# LLU_PCB_V2.net
KiCad netlist of a schematic drawn in EasyEDA
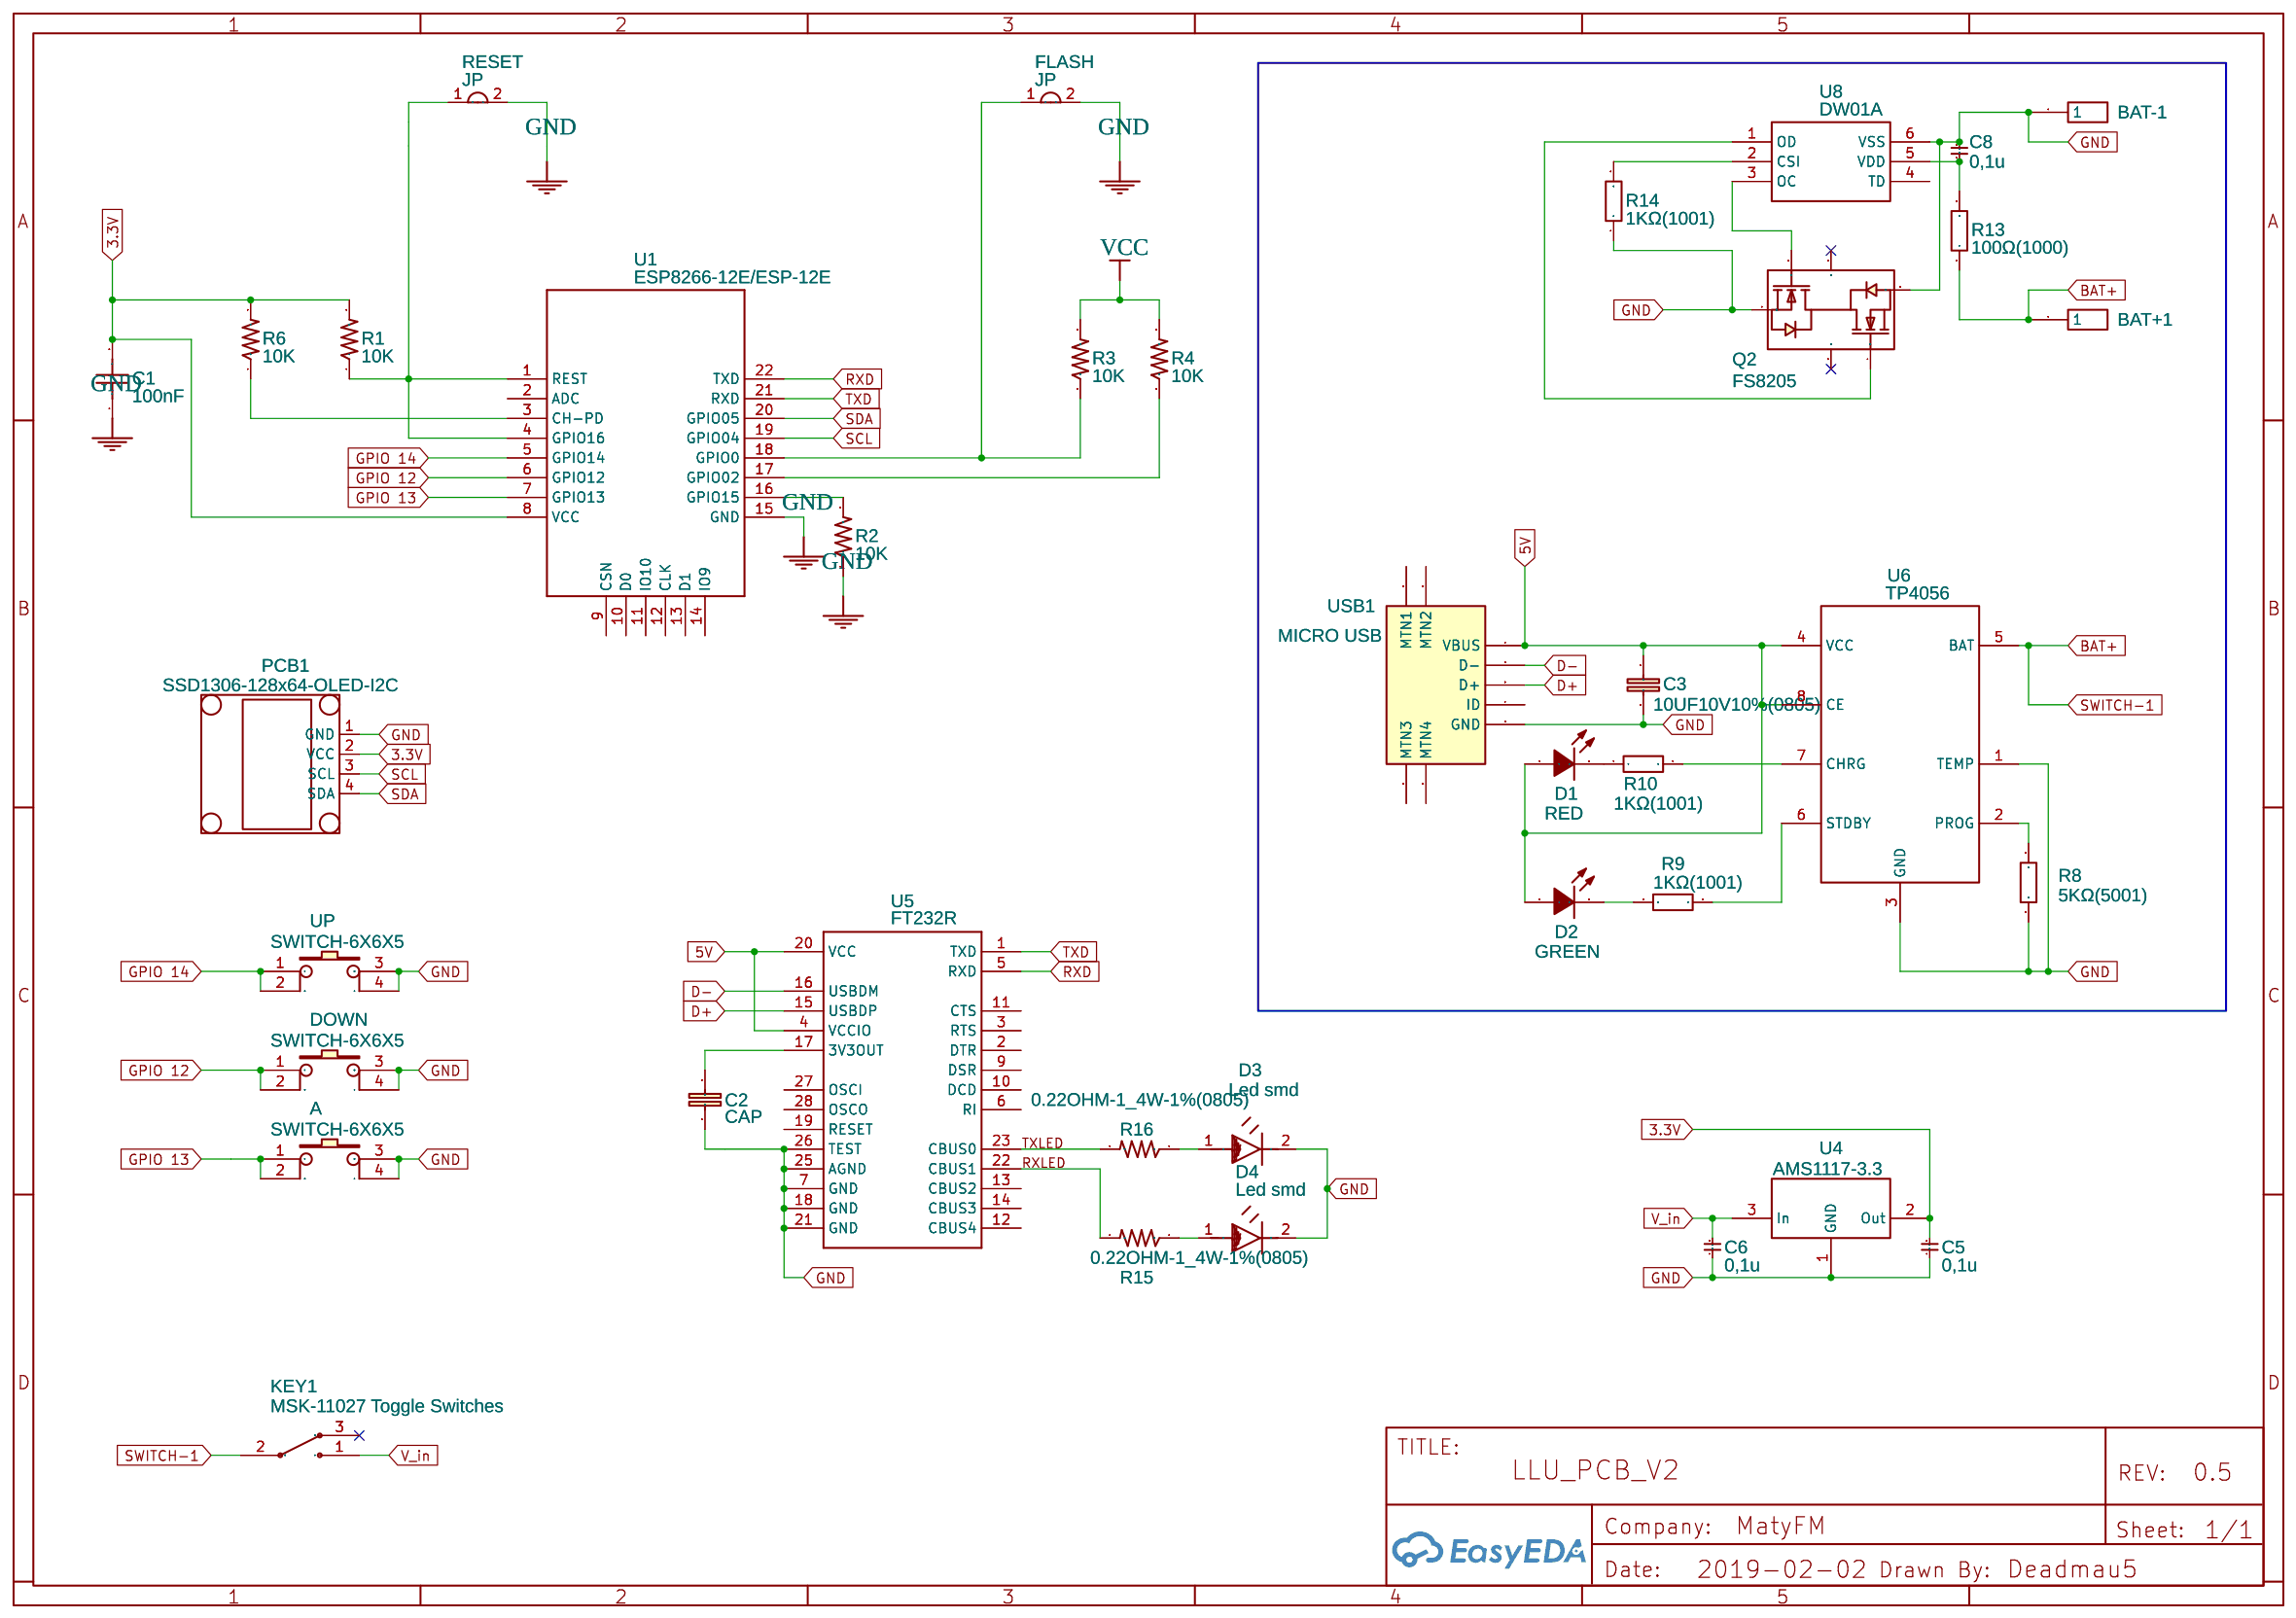
[diagram p0: schematic sheet]

(export (version "E")
  (design (tool "Eeschema 10.0.6"))
  (components
    (comp (ref "A")
      (value "SWITCH-6X6X5")
      (fields
        (field (name "BOM_Manufacturer Part") "SWITCH-6X6X5_TH")
        (field (name "BOM_Supplier Part") "C69330")
      )
      (libsource (lib "") (part "Unknown_155_590"))
    )
    (comp (ref "BAT+1")
      (value "BAT+")
      (fields
        (field (name "BOM_Manufacturer Part") "Header 1*1P")
        (field (name "BOM_Supplier Part") "C81276")
      )
      (libsource (lib "") (part "Unknown_1040_155"))
    )
    (comp (ref "BAT-1")
      (value "BAT-")
      (fields
        (field (name "BOM_Manufacturer Part") "Header 1*1P")
        (field (name "BOM_Supplier Part") "C81276")
      )
      (libsource (lib "") (part "Unknown_1040_50"))
    )
    (comp (ref "C1")
      (value "100nF")
      (fields
        (field (name "BOM_Manufacturer Part") "GRM2165C1H122JA01D")
        (field (name "BOM_Supplier Part") "C97898")
      )
      (libsource (lib "") (part "Capasitor_0805"))
    )
    (comp (ref "C2")
      (value "CAP")
      (fields (field (name "BOM_Manufacturer Part") "?"))
      (libsource (lib "") (part "Unknown_350_555"))
    )
    (comp (ref "C3")
      (value "10UF10V10%(0805)")
      (fields (field (name "BOM_Manufacturer Part") "?"))
      (libsource (lib "") (part "Unknown_825_345"))
    )
    (comp (ref "C5")
      (value "0,1u")
      (fields
        (field (name "BOM_Manufacturer Part") "0805F106M250NT")
        (field (name "BOM_Supplier Part") "C48181")
      )
      (libsource (lib "") (part "Unknown_970_620"))
    )
    (comp (ref "C6")
      (value "0,1u")
      (fields
        (field (name "BOM_Manufacturer Part") "0805F106M250NT")
        (field (name "BOM_Supplier Part") "C48181")
      )
      (libsource (lib "") (part "Unknown_860_620"))
    )
    (comp (ref "C8")
      (value "0,1u")
      (fields
        (field (name "BOM_Manufacturer Part") "0805F106M250NT")
        (field (name "BOM_Supplier Part") "C48181")
      )
      (libsource (lib "") (part "Unknown_985_65"))
    )
    (comp (ref "D1")
      (value "RED")
      (fields
        (field (name "BOM_Manufacturer Part") "LTST-C191KRKT")
        (field (name "BOM_Supplier Part") "C125099")
      )
      (libsource (lib "") (part "Unknown_785_375"))
    )
    (comp (ref "D2")
      (value "GREEN")
      (fields
        (field (name "BOM_Manufacturer Part") "LTST-C193TGKT-5A")
        (field (name "BOM_Supplier Part") "C12065")
      )
      (libsource (lib "") (part "Unknown_785_445"))
    )
    (comp (ref "D3") (value "Led smd") (libsource (lib "") (part "Unknown_600_575")))
    (comp (ref "D4") (value "Led smd") (libsource (lib "") (part "Unknown_600_620")))
    (comp (ref "DOWN")
      (value "SWITCH-6X6X5")
      (fields
        (field (name "BOM_Manufacturer Part") "SWITCH-6X6X5_TH")
        (field (name "BOM_Supplier Part") "C69330")
      )
      (libsource (lib "") (part "Unknown_155_545"))
    )
    (comp (ref "FLASH")
      (value "JP")
      (fields (field (name "BOM_Manufacturer Part") "SMD-Jumper"))
      (libsource (lib "") (part "Unknown_525_45"))
    )
    (comp (ref "KEY1") (value "MSK-11027 Toggle Switches") (libsource (lib "") (part "Unknown_155_720")))
    (comp (ref "PCB1")
      (value "SSD1306-128x64-OLED-I2C")
      (fields (field (name "BOM_Manufacturer Part") "?"))
      (libsource (lib "") (part "Unknown_135_375"))
    )
    (comp (ref "Q2")
      (value "FS8205")
      (fields (field (name "BOM_Supplier Part") "C32254"))
      (libsource (lib "") (part "Unknown_920_150"))
    )
    (comp (ref "R1")
      (value "10K")
      (fields (field (name "BOM_Manufacturer Part") "?"))
      (libsource (lib "") (part "Unknown_170_165"))
    )
    (comp (ref "R2")
      (value "10K")
      (fields (field (name "BOM_Manufacturer Part") "?"))
      (libsource (lib "") (part "Unknown_420_265"))
    )
    (comp (ref "R3")
      (value "10K")
      (fields (field (name "BOM_Manufacturer Part") "?"))
      (libsource (lib "") (part "Unknown_540_175"))
    )
    (comp (ref "R4")
      (value "10K")
      (fields (field (name "BOM_Manufacturer Part") "?"))
      (libsource (lib "") (part "Unknown_580_175"))
    )
    (comp (ref "R6")
      (value "10K")
      (fields (field (name "BOM_Manufacturer Part") "?"))
      (libsource (lib "") (part "Unknown_120_165"))
    )
    (comp (ref "R8")
      (value "5KΩ(5001)")
      (fields
        (field (name "BOM_Manufacturer Part") "RT0805BRD075K1L")
        (field (name "BOM_Supplier Part") "C122968")
      )
      (libsource (lib "") (part "RT0805BRD075K1L"))
    )
    (comp (ref "R9")
      (value "1KΩ(1001)")
      (fields
        (field (name "BOM_Manufacturer Part") "RT0805BRD071KL")
        (field (name "BOM_Supplier Part") "C110774")
      )
      (libsource (lib "") (part "RT0805BRD071KL"))
    )
    (comp (ref "R10")
      (value "1KΩ(1001)")
      (fields
        (field (name "BOM_Manufacturer Part") "RT0805BRD071KL")
        (field (name "BOM_Supplier Part") "C110774")
      )
      (libsource (lib "") (part "RT0805BRD071KL"))
    )
    (comp (ref "R13")
      (value "100Ω(1000)")
      (fields
        (field (name "BOM_Manufacturer Part") "CR0805F81000G")
        (field (name "BOM_Supplier Part") "C101403")
      )
      (libsource (lib "") (part "CR0805F81000G"))
    )
    (comp (ref "R14")
      (value "1KΩ(1001)")
      (fields
        (field (name "BOM_Manufacturer Part") "RTT051001FTP")
        (field (name "BOM_Supplier Part") "C103903")
      )
      (libsource (lib "") (part "RTT051001FTP"))
    )
    (comp (ref "R15")
      (value "0.22OHM-1_4W-1%(0805)")
      (fields (field (name "BOM_Manufacturer Part") "?"))
      (libsource (lib "") (part "Unknown_570_620"))
    )
    (comp (ref "R16")
      (value "0.22OHM-1_4W-1%(0805)")
      (fields (field (name "BOM_Manufacturer Part") "?"))
      (libsource (lib "") (part "Unknown_570_575"))
    )
    (comp (ref "RESET")
      (value "JP")
      (fields (field (name "BOM_Manufacturer Part") "SMD-Jumper"))
      (libsource (lib "") (part "Unknown_235_45"))
    )
    (comp (ref "U1")
      (value "ESP8266-12E/ESP-12E")
      (fields (field (name "BOM_Supplier Part") "317060015"))
      (libsource (lib "") (part "Unknown_320_235"))
    )
    (comp (ref "U4")
      (value "AMS1117-3.3")
      (fields (field (name "BOM_Manufacturer Part") "AMS1117-5.0") (field (name "BOM_Supplier Part") "C6187"))
      (libsource (lib "") (part "Unknown_920_610"))
    )
    (comp (ref "U5")
      (value "FT232R")
      (fields (field (name "BOM_Manufacturer Part") "?"))
      (libsource (lib "") (part "Unknown_450_545"))
    )
    (comp (ref "U6")
      (value "TP4056")
      (fields (field (name "BOM_Supplier Part") "C16581"))
      (libsource (lib "") (part "Unknown_955_380"))
    )
    (comp (ref "U8")
      (value "DW01A")
      (fields (field (name "BOM_Supplier Part") "C85680"))
      (libsource (lib "") (part "Unknown_920_75"))
    )
    (comp (ref "UP")
      (value "SWITCH-6X6X5")
      (fields
        (field (name "BOM_Manufacturer Part") "SWITCH-6X6X5_TH")
        (field (name "BOM_Supplier Part") "C69330")
      )
      (libsource (lib "") (part "Unknown_155_495"))
    )
    (comp (ref "USB1")
      (value "MICRO USB")
      (fields
        (field (name "BOM_Manufacturer Part") "MICRO USB 5S B")
        (field (name "BOM_Supplier Part") "C10418")
      )
      (libsource (lib "") (part "Unknown_715_340"))
    )
  )
  (nets
    (net (code "1") (name "3.3V") (class "Default")
      (node (ref "C1") (pin "2") (pinfunction "2_2") (pintype "unspecified"))
      (node (ref "C5") (pin "2") (pinfunction "2_2") (pintype "input"))
      (node (ref "PCB1") (pin "2") (pinfunction "VCC_2") (pintype "input"))
      (node (ref "R1") (pin "2") (pinfunction "2_2") (pintype "unspecified"))
      (node (ref "R6") (pin "2") (pinfunction "2_2") (pintype "unspecified"))
      (node (ref "U1") (pin "8") (pinfunction "VCC_8") (pintype "unspecified"))
      (node (ref "U4") (pin "2") (pinfunction "Out_2") (pintype "unspecified"))
    )
    (net (code "2") (name "5V") (class "Default")
      (node (ref "C3") (pin "1") (pinfunction "1_1") (pintype "unspecified"))
      (node (ref "D1") (pin "1") (pinfunction "A_1") (pintype "unspecified"))
      (node (ref "D2") (pin "1") (pinfunction "A_1") (pintype "unspecified"))
      (node (ref "U5") (pin "20") (pinfunction "VCC_20") (pintype "passive"))
      (node (ref "U5") (pin "4") (pinfunction "VCCIO_4") (pintype "passive"))
      (node (ref "U6") (pin "4") (pinfunction "VCC_4") (pintype "unspecified"))
      (node (ref "U6") (pin "8") (pinfunction "CE_8") (pintype "unspecified"))
      (node (ref "USB1") (pin "1") (pinfunction "VBUS_1") (pintype "input"))
    )
    (net (code "3") (name "BAT+") (class "Default")
      (node (ref "BAT+1") (pin "1") (pinfunction "1_1") (pintype "input"))
      (node (ref "KEY1") (pin "2") (pinfunction "2_2") (pintype "unspecified"))
      (node (ref "R13") (pin "1") (pinfunction "1_1") (pintype "input"))
      (node (ref "U6") (pin "5") (pinfunction "BAT_5") (pintype "unspecified"))
    )
    (net (code "4") (name "D+") (class "Default")
      (node (ref "U5") (pin "15") (pinfunction "USBDP_15") (pintype "unspecified"))
      (node (ref "USB1") (pin "3") (pinfunction "D+_3") (pintype "input"))
    )
    (net (code "5") (name "D-") (class "Default")
      (node (ref "U5") (pin "16") (pinfunction "USBDM_16") (pintype "unspecified"))
      (node (ref "USB1") (pin "2") (pinfunction "D-_2") (pintype "input"))
    )
    (net (code "6") (name "GND") (class "Default")
      (node (ref "A") (pin "3") (pinfunction "3_3") (pintype "input"))
      (node (ref "A") (pin "4") (pinfunction "4_4") (pintype "input"))
      (node (ref "BAT-1") (pin "1") (pinfunction "1_1") (pintype "input"))
      (node (ref "C1") (pin "1") (pinfunction "1_1") (pintype "unspecified"))
      (node (ref "C2") (pin "2") (pinfunction "2_2") (pintype "unspecified"))
      (node (ref "C3") (pin "2") (pinfunction "2_2") (pintype "unspecified"))
      (node (ref "C5") (pin "1") (pinfunction "1_1") (pintype "input"))
      (node (ref "C6") (pin "1") (pinfunction "1_1") (pintype "input"))
      (node (ref "C8") (pin "2") (pinfunction "2_2") (pintype "input"))
      (node (ref "D3") (pin "2") (pinfunction "2_2") (pintype "unspecified"))
      (node (ref "D4") (pin "2") (pinfunction "2_2") (pintype "unspecified"))
      (node (ref "DOWN") (pin "3") (pinfunction "3_3") (pintype "input"))
      (node (ref "DOWN") (pin "4") (pinfunction "4_4") (pintype "input"))
      (node (ref "FLASH") (pin "2") (pinfunction "2_2") (pintype "unspecified"))
      (node (ref "PCB1") (pin "1") (pinfunction "GND_1") (pintype "input"))
      (node (ref "Q2") (pin "1") (pinfunction "S1_1") (pintype "unspecified"))
      (node (ref "Q2") (pin "3") (pinfunction "S2_3") (pintype "unspecified"))
      (node (ref "R14") (pin "1") (pinfunction "1_1") (pintype "input"))
      (node (ref "R2") (pin "1") (pinfunction "1_1") (pintype "unspecified"))
      (node (ref "R8") (pin "1") (pinfunction "1_1") (pintype "input"))
      (node (ref "RESET") (pin "2") (pinfunction "2_2") (pintype "unspecified"))
      (node (ref "U1") (pin "15") (pinfunction "GND_15") (pintype "unspecified"))
      (node (ref "U4") (pin "1") (pinfunction "GND_1") (pintype "unspecified"))
      (node (ref "U5") (pin "18") (pinfunction "GND_18") (pintype "passive"))
      (node (ref "U5") (pin "21") (pinfunction "GND_21") (pintype "passive"))
      (node (ref "U5") (pin "25") (pinfunction "AGND_25") (pintype "passive"))
      (node (ref "U5") (pin "26") (pinfunction "TEST_26") (pintype "input"))
      (node (ref "U5") (pin "7") (pinfunction "GND_7") (pintype "passive"))
      (node (ref "U6") (pin "1") (pinfunction "TEMP_1") (pintype "unspecified"))
      (node (ref "U6") (pin "3") (pinfunction "GND_3") (pintype "unspecified"))
      (node (ref "U8") (pin "6") (pinfunction "VSS_6") (pintype "unspecified"))
      (node (ref "UP") (pin "3") (pinfunction "3_3") (pintype "input"))
      (node (ref "UP") (pin "4") (pinfunction "4_4") (pintype "input"))
      (node (ref "USB1") (pin "5") (pinfunction "GND_5") (pintype "input"))
    )
    (net (code "7") (name "GPIO 12") (class "Default")
      (node (ref "DOWN") (pin "1") (pinfunction "1_1") (pintype "input"))
      (node (ref "DOWN") (pin "2") (pinfunction "2_2") (pintype "input"))
      (node (ref "U1") (pin "6") (pinfunction "GPIO12_6") (pintype "unspecified"))
    )
    (net (code "8") (name "GPIO 13") (class "Default")
      (node (ref "A") (pin "1") (pinfunction "1_1") (pintype "input"))
      (node (ref "A") (pin "2") (pinfunction "2_2") (pintype "input"))
      (node (ref "U1") (pin "7") (pinfunction "GPIO13_7") (pintype "unspecified"))
    )
    (net (code "9") (name "GPIO 14") (class "Default")
      (node (ref "U1") (pin "5") (pinfunction "GPIO14_5") (pintype "unspecified"))
      (node (ref "UP") (pin "1") (pinfunction "1_1") (pintype "input"))
      (node (ref "UP") (pin "2") (pinfunction "2_2") (pintype "input"))
    )
    (net (code "10") (name "Net-(D1-K)") (class "Default")
      (node (ref "D1") (pin "2") (pinfunction "K_2") (pintype "unspecified"))
      (node (ref "R10") (pin "1") (pinfunction "1_1") (pintype "input"))
    )
    (net (code "11") (name "Net-(D2-K)") (class "Default")
      (node (ref "D2") (pin "2") (pinfunction "K_2") (pintype "unspecified"))
      (node (ref "R9") (pin "1") (pinfunction "1_1") (pintype "input"))
    )
    (net (code "12") (name "Net-(D3-Pad1)") (class "Default")
      (node (ref "D3") (pin "1") (pinfunction "1_1") (pintype "unspecified"))
      (node (ref "R16") (pin "1") (pinfunction "1_1") (pintype "unspecified"))
    )
    (net (code "13") (name "Net-(D4-Pad1)") (class "Default")
      (node (ref "D4") (pin "1") (pinfunction "1_1") (pintype "unspecified"))
      (node (ref "R15") (pin "1") (pinfunction "1_1") (pintype "unspecified"))
    )
    (net (code "14") (name "Net-(Q2-G1)") (class "Default")
      (node (ref "Q2") (pin "6") (pinfunction "G1_6") (pintype "unspecified"))
      (node (ref "U8") (pin "3") (pinfunction "OC_3") (pintype "unspecified"))
    )
    (net (code "15") (name "Net-(Q2-G2)") (class "Default")
      (node (ref "Q2") (pin "4") (pinfunction "G2_4") (pintype "unspecified"))
      (node (ref "U8") (pin "1") (pinfunction "OD_1") (pintype "unspecified"))
    )
    (net (code "16") (name "Net-(U1-CH-PD)") (class "Default")
      (node (ref "R6") (pin "1") (pinfunction "1_1") (pintype "unspecified"))
      (node (ref "U1") (pin "3") (pinfunction "CH-PD_3") (pintype "unspecified"))
    )
    (net (code "17") (name "Net-(U1-GPIO0)") (class "Default")
      (node (ref "FLASH") (pin "1") (pinfunction "1_1") (pintype "unspecified"))
      (node (ref "R3") (pin "1") (pinfunction "1_1") (pintype "unspecified"))
      (node (ref "U1") (pin "18") (pinfunction "GPIO0_18") (pintype "unspecified"))
    )
    (net (code "18") (name "Net-(U1-GPIO02)") (class "Default")
      (node (ref "R4") (pin "1") (pinfunction "1_1") (pintype "unspecified"))
      (node (ref "U1") (pin "17") (pinfunction "GPIO02_17") (pintype "unspecified"))
    )
    (net (code "19") (name "Net-(U1-GPIO15)") (class "Default")
      (node (ref "R2") (pin "2") (pinfunction "2_2") (pintype "unspecified"))
      (node (ref "U1") (pin "16") (pinfunction "GPIO15_16") (pintype "unspecified"))
    )
    (net (code "20") (name "Net-(U1-GPIO16)") (class "Default")
      (node (ref "R1") (pin "1") (pinfunction "1_1") (pintype "unspecified"))
      (node (ref "RESET") (pin "1") (pinfunction "1_1") (pintype "unspecified"))
      (node (ref "U1") (pin "1") (pinfunction "REST_1") (pintype "unspecified"))
      (node (ref "U1") (pin "4") (pinfunction "GPIO16_4") (pintype "unspecified"))
    )
    (net (code "21") (name "Net-(U5-3V3OUT)") (class "Default")
      (node (ref "C2") (pin "1") (pinfunction "1_1") (pintype "unspecified"))
      (node (ref "U5") (pin "17") (pinfunction "3V3OUT_17") (pintype "output"))
    )
    (net (code "22") (name "Net-(U5-CBUS0)") (class "Default")
      (node (ref "R16") (pin "2") (pinfunction "2_2") (pintype "unspecified"))
      (node (ref "U5") (pin "23") (pinfunction "CBUS0_23") (pintype "input"))
    )
    (net (code "23") (name "Net-(U5-CBUS1)") (class "Default")
      (node (ref "R15") (pin "2") (pinfunction "2_2") (pintype "unspecified"))
      (node (ref "U5") (pin "22") (pinfunction "CBUS1_22") (pintype "input"))
    )
    (net (code "24") (name "Net-(U6-CHRG)") (class "Default")
      (node (ref "R10") (pin "2") (pinfunction "2_2") (pintype "input"))
      (node (ref "U6") (pin "7") (pinfunction "CHRG_7") (pintype "unspecified"))
    )
    (net (code "25") (name "Net-(U6-PROG)") (class "Default")
      (node (ref "R8") (pin "2") (pinfunction "2_2") (pintype "input"))
      (node (ref "U6") (pin "2") (pinfunction "PROG_2") (pintype "unspecified"))
    )
    (net (code "26") (name "Net-(U6-STDBY)") (class "Default")
      (node (ref "R9") (pin "2") (pinfunction "2_2") (pintype "input"))
      (node (ref "U6") (pin "6") (pinfunction "STDBY_6") (pintype "unspecified"))
    )
    (net (code "27") (name "Net-(U8-CSI)") (class "Default")
      (node (ref "R14") (pin "2") (pinfunction "2_2") (pintype "input"))
      (node (ref "U8") (pin "2") (pinfunction "CSI_2") (pintype "unspecified"))
    )
    (net (code "28") (name "Net-(U8-VDD)") (class "Default")
      (node (ref "C8") (pin "1") (pinfunction "1_1") (pintype "input"))
      (node (ref "R13") (pin "2") (pinfunction "2_2") (pintype "input"))
      (node (ref "U8") (pin "5") (pinfunction "VDD_5") (pintype "unspecified"))
    )
    (net (code "29") (name "RXD") (class "Default")
      (node (ref "U1") (pin "22") (pinfunction "TXD_22") (pintype "unspecified"))
      (node (ref "U5") (pin "5") (pinfunction "RXD_5") (pintype "input"))
    )
    (net (code "30") (name "SCL") (class "Default")
      (node (ref "PCB1") (pin "3") (pinfunction "SCL_3") (pintype "passive"))
      (node (ref "U1") (pin "19") (pinfunction "GPIO04_19") (pintype "unspecified"))
    )
    (net (code "31") (name "SDA") (class "Default")
      (node (ref "PCB1") (pin "4") (pinfunction "SDA_4") (pintype "passive"))
      (node (ref "U1") (pin "20") (pinfunction "GPIO05_20") (pintype "unspecified"))
    )
    (net (code "32") (name "TXD") (class "Default")
      (node (ref "U1") (pin "21") (pinfunction "RXD_21") (pintype "unspecified"))
      (node (ref "U5") (pin "1") (pinfunction "TXD_1") (pintype "output"))
    )
    (net (code "33") (name "VCC") (class "Default")
      (node (ref "R3") (pin "2") (pinfunction "2_2") (pintype "unspecified"))
      (node (ref "R4") (pin "2") (pinfunction "2_2") (pintype "unspecified"))
    )
    (net (code "34") (name "V_in") (class "Default")
      (node (ref "C6") (pin "2") (pinfunction "2_2") (pintype "input"))
      (node (ref "KEY1") (pin "1") (pinfunction "1_1") (pintype "unspecified"))
      (node (ref "U4") (pin "3") (pinfunction "In_3") (pintype "unspecified"))
    )
    (net (code "35") (name "unconnected-(KEY1-Pad3)") (class "Default")
      (node (ref "KEY1") (pin "3") (pinfunction "3_3") (pintype "unspecified+no_connect"))
    )
    (net (code "36") (name "unconnected-(Q2-D12-Pad2)") (class "Default")
      (node (ref "Q2") (pin "2") (pinfunction "D12_2") (pintype "unspecified+no_connect"))
    )
    (net (code "37") (name "unconnected-(Q2-D12-Pad5)") (class "Default")
      (node (ref "Q2") (pin "5") (pinfunction "D12_5") (pintype "unspecified+no_connect"))
    )
    (net (code "38") (name "unconnected-(U1-ADC-Pad2)") (class "Default")
      (node (ref "U1") (pin "2") (pinfunction "ADC_2") (pintype "unspecified"))
    )
    (net (code "39") (name "unconnected-(U1-CLK-Pad12)") (class "Default")
      (node (ref "U1") (pin "12") (pinfunction "CLK_12") (pintype "unspecified"))
    )
    (net (code "40") (name "unconnected-(U1-CSN-Pad9)") (class "Default")
      (node (ref "U1") (pin "9") (pinfunction "CSN_9") (pintype "unspecified"))
    )
    (net (code "41") (name "unconnected-(U1-D0-Pad10)") (class "Default")
      (node (ref "U1") (pin "10") (pinfunction "D0_10") (pintype "unspecified"))
    )
    (net (code "42") (name "unconnected-(U1-D1-Pad13)") (class "Default")
      (node (ref "U1") (pin "13") (pinfunction "D1_13") (pintype "unspecified"))
    )
    (net (code "43") (name "unconnected-(U1-IO9-Pad14)") (class "Default")
      (node (ref "U1") (pin "14") (pinfunction "IO9_14") (pintype "unspecified"))
    )
    (net (code "44") (name "unconnected-(U1-IO10-Pad11)") (class "Default")
      (node (ref "U1") (pin "11") (pinfunction "IO10_11") (pintype "unspecified"))
    )
    (net (code "45") (name "unconnected-(U5-CBUS2-Pad13)") (class "Default")
      (node (ref "U5") (pin "13") (pinfunction "CBUS2_13") (pintype "input"))
    )
    (net (code "46") (name "unconnected-(U5-CBUS3-Pad14)") (class "Default")
      (node (ref "U5") (pin "14") (pinfunction "CBUS3_14") (pintype "input"))
    )
    (net (code "47") (name "unconnected-(U5-CBUS4-Pad12)") (class "Default")
      (node (ref "U5") (pin "12") (pinfunction "CBUS4_12") (pintype "input"))
    )
    (net (code "48") (name "unconnected-(U5-CTS-Pad11)") (class "Default")
      (node (ref "U5") (pin "11") (pinfunction "CTS_11") (pintype "input"))
    )
    (net (code "49") (name "unconnected-(U5-DCD-Pad10)") (class "Default")
      (node (ref "U5") (pin "10") (pinfunction "DCD_10") (pintype "input"))
    )
    (net (code "50") (name "unconnected-(U5-DSR-Pad9)") (class "Default")
      (node (ref "U5") (pin "9") (pinfunction "DSR_9") (pintype "input"))
    )
    (net (code "51") (name "unconnected-(U5-DTR-Pad2)") (class "Default")
      (node (ref "U5") (pin "2") (pinfunction "DTR_2") (pintype "output"))
    )
    (net (code "52") (name "unconnected-(U5-OSCI-Pad27)") (class "Default")
      (node (ref "U5") (pin "27") (pinfunction "OSCI_27") (pintype "input"))
    )
    (net (code "53") (name "unconnected-(U5-OSCO-Pad28)") (class "Default")
      (node (ref "U5") (pin "28") (pinfunction "OSCO_28") (pintype "output"))
    )
    (net (code "54") (name "unconnected-(U5-RESET-Pad19)") (class "Default")
      (node (ref "U5") (pin "19") (pinfunction "RESET_19") (pintype "input"))
    )
    (net (code "55") (name "unconnected-(U5-RI-Pad6)") (class "Default")
      (node (ref "U5") (pin "6") (pinfunction "RI_6") (pintype "input"))
    )
    (net (code "56") (name "unconnected-(U5-RTS-Pad3)") (class "Default")
      (node (ref "U5") (pin "3") (pinfunction "RTS_3") (pintype "output"))
    )
    (net (code "57") (name "unconnected-(U8-TD-Pad4)") (class "Default")
      (node (ref "U8") (pin "4") (pinfunction "TD_4") (pintype "unspecified"))
    )
    (net (code "58") (name "unconnected-(USB1-ID-Pad4)") (class "Default")
      (node (ref "USB1") (pin "4") (pinfunction "ID_4") (pintype "input"))
    )
    (net (code "59") (name "unconnected-(USB1-MTN1-Pad0)") (class "Default")
      (node (ref "USB1") (pin "0") (pinfunction "MTN1_0") (pintype "input"))
    )
    (net (code "60") (name "unconnected-(USB1-MTN2-Pad0)") (class "Default")
      (node (ref "USB1") (pin "0") (pinfunction "MTN2_0") (pintype "input"))
    )
    (net (code "61") (name "unconnected-(USB1-MTN3-Pad0)") (class "Default")
      (node (ref "USB1") (pin "0") (pinfunction "MTN3_0") (pintype "input"))
    )
    (net (code "62") (name "unconnected-(USB1-MTN4-Pad0)") (class "Default")
      (node (ref "USB1") (pin "0") (pinfunction "MTN4_0") (pintype "input"))
    )
  )
)
